# pro-micro-ora.net
KiCad netlist of a schematic drawn in EAGLE
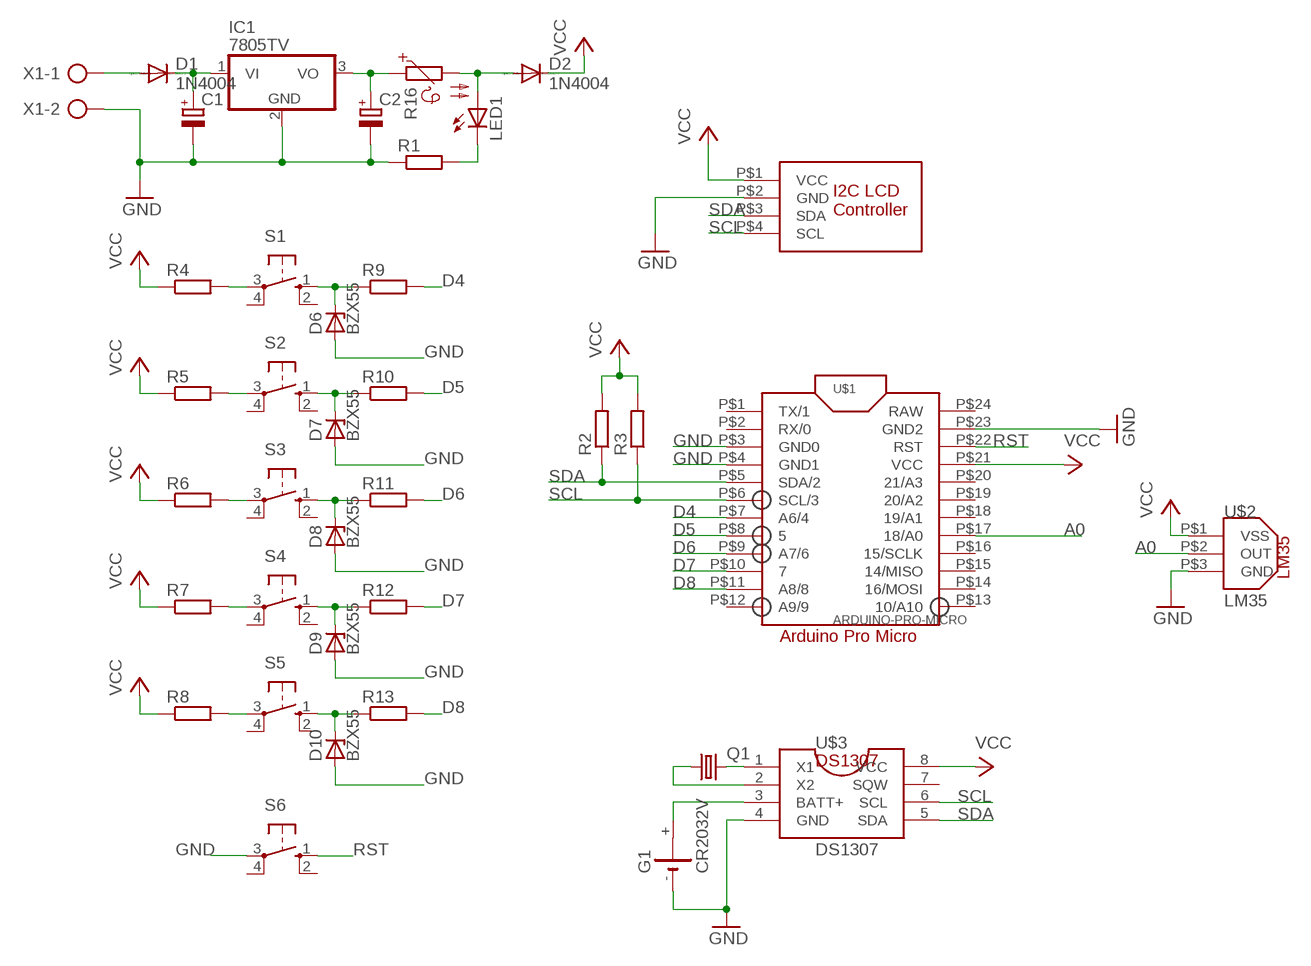
[diagram p0: schematic, sheet 1]

(export (version "E")
  (design (tool "Eeschema 10.0.6"))
  (components
    (comp (ref "C1")
      (value "CPOL-EUE2.5-5")
      (footprint "eagle-import:E2,5-5")
      (libsource (lib "eagle-import") (part "CPOL-EUE2.5-5"))
    )
    (comp (ref "C2")
      (value "CPOL-EUE2.5-5")
      (footprint "eagle-import:E2,5-5")
      (libsource (lib "eagle-import") (part "CPOL-EUE2.5-5"))
    )
    (comp (ref "D1")
      (value "1N4004")
      (footprint "eagle-import:DO41-10")
      (libsource (lib "eagle-import") (part "1N4004"))
    )
    (comp (ref "D2")
      (value "1N4004")
      (footprint "eagle-import:DO41-10")
      (libsource (lib "eagle-import") (part "1N4004"))
    )
    (comp (ref "D6")
      (value "BZX55")
      (footprint "eagle-import:DO35Z10")
      (libsource (lib "eagle-import") (part "BZX55"))
    )
    (comp (ref "D7")
      (value "BZX55")
      (footprint "eagle-import:DO35Z10")
      (libsource (lib "eagle-import") (part "BZX55"))
    )
    (comp (ref "D8")
      (value "BZX55")
      (footprint "eagle-import:DO35Z10")
      (libsource (lib "eagle-import") (part "BZX55"))
    )
    (comp (ref "D9")
      (value "BZX55")
      (footprint "eagle-import:DO35Z10")
      (libsource (lib "eagle-import") (part "BZX55"))
    )
    (comp (ref "D10")
      (value "BZX55")
      (footprint "eagle-import:DO35Z10")
      (libsource (lib "eagle-import") (part "BZX55"))
    )
    (comp (ref "G1")
      (value "CR2032V")
      (footprint "eagle-import:CR2032V")
      (libsource (lib "eagle-import") (part "CR2032V"))
    )
    (comp (ref "IC1")
      (value "7805TV")
      (footprint "eagle-import:TO220V")
      (libsource (lib "eagle-import") (part "78TV05"))
    )
    (comp (ref "LED1")
      (value "LED5MM")
      (footprint "eagle-import:LED5MM")
      (libsource (lib "eagle-import") (part "LED5MM"))
    )
    (comp (ref "Q1")
      (value "CRYSTALTC26H")
      (footprint "eagle-import:TC26H")
      (libsource (lib "eagle-import") (part "CRYSTALTC26H"))
    )
    (comp (ref "R1")
      (value "R-EU_0204/7")
      (footprint "eagle-import:0204_7")
      (libsource (lib "eagle-import") (part "R-EU_0204/7"))
    )
    (comp (ref "R2")
      (value "R-EU_0204/7")
      (footprint "eagle-import:0204_7")
      (libsource (lib "eagle-import") (part "R-EU_0204/7"))
    )
    (comp (ref "R3")
      (value "R-EU_0204/7")
      (footprint "eagle-import:0204_7")
      (libsource (lib "eagle-import") (part "R-EU_0204/7"))
    )
    (comp (ref "R4")
      (value "R-EU_0204/7")
      (footprint "eagle-import:0204_7")
      (libsource (lib "eagle-import") (part "R-EU_0204/7"))
    )
    (comp (ref "R5")
      (value "R-EU_0204/7")
      (footprint "eagle-import:0204_7")
      (libsource (lib "eagle-import") (part "R-EU_0204/7"))
    )
    (comp (ref "R6")
      (value "R-EU_0204/7")
      (footprint "eagle-import:0204_7")
      (libsource (lib "eagle-import") (part "R-EU_0204/7"))
    )
    (comp (ref "R7")
      (value "R-EU_0204/7")
      (footprint "eagle-import:0204_7")
      (libsource (lib "eagle-import") (part "R-EU_0204/7"))
    )
    (comp (ref "R8")
      (value "R-EU_0204/7")
      (footprint "eagle-import:0204_7")
      (libsource (lib "eagle-import") (part "R-EU_0204/7"))
    )
    (comp (ref "R9")
      (value "R-EU_0204/7")
      (footprint "eagle-import:0204_7")
      (libsource (lib "eagle-import") (part "R-EU_0204/7"))
    )
    (comp (ref "R10")
      (value "R-EU_0204/7")
      (footprint "eagle-import:0204_7")
      (libsource (lib "eagle-import") (part "R-EU_0204/7"))
    )
    (comp (ref "R11")
      (value "R-EU_0204/7")
      (footprint "eagle-import:0204_7")
      (libsource (lib "eagle-import") (part "R-EU_0204/7"))
    )
    (comp (ref "R12")
      (value "R-EU_0204/7")
      (footprint "eagle-import:0204_7")
      (libsource (lib "eagle-import") (part "R-EU_0204/7"))
    )
    (comp (ref "R13")
      (value "R-EU_0204/7")
      (footprint "eagle-import:0204_7")
      (libsource (lib "eagle-import") (part "R-EU_0204/7"))
    )
    (comp (ref "R16")
      (value "PTC660")
      (footprint "eagle-import:P660")
      (libsource (lib "eagle-import") (part "PTC660"))
    )
    (comp (ref "S1")
      (value "10-XX")
      (footprint "eagle-import:B3F-10XX")
      (fields (field (name "MPN") "B3F-1000"))
      (libsource (lib "eagle-import") (part "10-XX"))
    )
    (comp (ref "S2")
      (value "10-XX")
      (footprint "eagle-import:B3F-10XX")
      (fields (field (name "MPN") "B3F-1000"))
      (libsource (lib "eagle-import") (part "10-XX"))
    )
    (comp (ref "S3")
      (value "10-XX")
      (footprint "eagle-import:B3F-10XX")
      (fields (field (name "MPN") "B3F-1000"))
      (libsource (lib "eagle-import") (part "10-XX"))
    )
    (comp (ref "S4")
      (value "10-XX")
      (footprint "eagle-import:B3F-10XX")
      (fields (field (name "MPN") "B3F-1000"))
      (libsource (lib "eagle-import") (part "10-XX"))
    )
    (comp (ref "S5")
      (value "10-XX")
      (footprint "eagle-import:B3F-10XX")
      (fields (field (name "MPN") "B3F-1000"))
      (libsource (lib "eagle-import") (part "10-XX"))
    )
    (comp (ref "S6")
      (value "10-XX")
      (footprint "eagle-import:B3F-10XX")
      (fields (field (name "MPN") "B3F-1000"))
      (libsource (lib "eagle-import") (part "10-XX"))
    )
    (comp (ref "U$1")
      (value "ARDUINO-PRO-MICRO")
      (footprint "eagle-import:ARDUINO-PRO-MICRO")
      (libsource (lib "eagle-import") (part "ARDUINO-PRO-MICRO"))
    )
    (comp (ref "U$2")
      (value "LM35")
      (footprint "eagle-import:LM35")
      (libsource (lib "eagle-import") (part "LM35"))
    )
    (comp (ref "U$3")
      (value "DS1307")
      (footprint "eagle-import:DS1307")
      (libsource (lib "eagle-import") (part "DS1307"))
    )
    (comp (ref "U$4")
      (value "I2C_LCD")
      (footprint "eagle-import:I2C_LCD")
      (libsource (lib "eagle-import") (part "I2C_LCD"))
    )
    (comp (ref "X1")
      (value "AK500/2")
      (footprint "eagle-import:AK500_2")
      (libsource (lib "eagle-import") (part "AK500/2"))
    )
  )
  (nets
    (net (code "1") (name "/A0") (class "Default")
      (node (ref "U$1") (pin "P$17") (pinfunction "18/A0_P$17") (pintype "bidirectional"))
      (node (ref "U$2") (pin "P$2") (pinfunction "OUT_P$2") (pintype "output"))
    )
    (net (code "2") (name "/D4") (class "Default")
      (node (ref "R9") (pin "2") (pinfunction "2_2") (pintype "passive"))
      (node (ref "U$1") (pin "P$7") (pinfunction "A6/4_P$7") (pintype "bidirectional"))
    )
    (net (code "3") (name "/D5") (class "Default")
      (node (ref "R10") (pin "2") (pinfunction "2_2") (pintype "passive"))
      (node (ref "U$1") (pin "P$8") (pinfunction "5_P$8") (pintype "bidirectional"))
    )
    (net (code "4") (name "/D6") (class "Default")
      (node (ref "R11") (pin "2") (pinfunction "2_2") (pintype "passive"))
      (node (ref "U$1") (pin "P$9") (pinfunction "A7/6_P$9") (pintype "bidirectional"))
    )
    (net (code "5") (name "/D7") (class "Default")
      (node (ref "R12") (pin "2") (pinfunction "2_2") (pintype "passive"))
      (node (ref "U$1") (pin "P$10") (pinfunction "7_P$10") (pintype "bidirectional"))
    )
    (net (code "6") (name "/D8") (class "Default")
      (node (ref "R13") (pin "2") (pinfunction "2_2") (pintype "passive"))
      (node (ref "U$1") (pin "P$11") (pinfunction "A8/8_P$11") (pintype "bidirectional"))
    )
    (net (code "7") (name "/RAW") (class "Default")
      (node (ref "U$1") (pin "P$24") (pinfunction "RAW_P$24") (pintype "power_in"))
    )
    (net (code "8") (name "/RST") (class "Default")
      (node (ref "S6") (pin "1") (pinfunction "S_1") (pintype "passive"))
      (node (ref "U$1") (pin "P$22") (pinfunction "RST_P$22") (pintype "bidirectional"))
    )
    (net (code "9") (name "/SCL") (class "Default")
      (node (ref "R3") (pin "1") (pinfunction "1_1") (pintype "passive"))
      (node (ref "U$1") (pin "P$6") (pinfunction "SCL/3_P$6") (pintype "bidirectional"))
      (node (ref "U$3") (pin "6") (pinfunction "SCL_6") (pintype "bidirectional"))
      (node (ref "U$4") (pin "P$4") (pinfunction "SCL_P$4") (pintype "bidirectional"))
    )
    (net (code "10") (name "/SDA") (class "Default")
      (node (ref "R2") (pin "1") (pinfunction "1_1") (pintype "passive"))
      (node (ref "U$1") (pin "P$5") (pinfunction "SDA/2_P$5") (pintype "bidirectional"))
      (node (ref "U$3") (pin "5") (pinfunction "SDA_5") (pintype "bidirectional"))
      (node (ref "U$4") (pin "P$3") (pinfunction "SDA_P$3") (pintype "bidirectional"))
    )
    (net (code "11") (name "GND") (class "Default")
      (node (ref "C1") (pin "-") (pinfunction "-_-") (pintype "passive"))
      (node (ref "C2") (pin "-") (pinfunction "-_-") (pintype "passive"))
      (node (ref "D10") (pin "A") (pinfunction "A_A") (pintype "passive"))
      (node (ref "D6") (pin "A") (pinfunction "A_A") (pintype "passive"))
      (node (ref "D7") (pin "A") (pinfunction "A_A") (pintype "passive"))
      (node (ref "D8") (pin "A") (pinfunction "A_A") (pintype "passive"))
      (node (ref "D9") (pin "A") (pinfunction "A_A") (pintype "passive"))
      (node (ref "G1") (pin "-") (pinfunction "-_-") (pintype "passive"))
      (node (ref "IC1") (pin "2") (pinfunction "GND_2") (pintype "passive"))
      (node (ref "R1") (pin "1") (pinfunction "1_1") (pintype "passive"))
      (node (ref "S6") (pin "3") (pinfunction "P_3") (pintype "passive"))
      (node (ref "U$1") (pin "P$23") (pinfunction "GND2_P$23") (pintype "power_in"))
      (node (ref "U$1") (pin "P$3") (pinfunction "GND0_P$3") (pintype "power_in"))
      (node (ref "U$1") (pin "P$4") (pinfunction "GND1_P$4") (pintype "power_in"))
      (node (ref "U$2") (pin "P$3") (pinfunction "GND_P$3") (pintype "power_in"))
      (node (ref "U$3") (pin "4") (pinfunction "GND_4") (pintype "bidirectional"))
      (node (ref "U$4") (pin "P$2") (pinfunction "GND_P$2") (pintype "bidirectional"))
      (node (ref "X1") (pin "2") (pinfunction "KL_2") (pintype "passive"))
    )
    (net (code "12") (name "Net-(D2-PadA)") (class "Default")
      (node (ref "D2") (pin "A") (pinfunction "A_A") (pintype "passive"))
      (node (ref "LED1") (pin "A") (pinfunction "A_A") (pintype "passive"))
      (node (ref "R16") (pin "2") (pinfunction "2_2") (pintype "passive"))
    )
    (net (code "13") (name "Net-(IC1-VI)") (class "Default")
      (node (ref "C1") (pin "+") (pinfunction "+_+") (pintype "passive"))
      (node (ref "D1") (pin "C") (pinfunction "C_C") (pintype "passive"))
      (node (ref "IC1") (pin "1") (pinfunction "VI_1") (pintype "input"))
    )
    (net (code "14") (name "Net-(IC1-VO)") (class "Default")
      (node (ref "C2") (pin "+") (pinfunction "+_+") (pintype "passive"))
      (node (ref "IC1") (pin "3") (pinfunction "VO_3") (pintype "passive"))
      (node (ref "R16") (pin "1") (pinfunction "1_1") (pintype "passive"))
    )
    (net (code "15") (name "Net-(LED1-C)") (class "Default")
      (node (ref "LED1") (pin "K") (pinfunction "C_K") (pintype "passive"))
      (node (ref "R1") (pin "2") (pinfunction "2_2") (pintype "passive"))
    )
    (net (code "16") (name "Net-(S1-P)") (class "Default")
      (node (ref "R4") (pin "2") (pinfunction "2_2") (pintype "passive"))
      (node (ref "S1") (pin "3") (pinfunction "P_3") (pintype "passive"))
    )
    (net (code "17") (name "Net-(S1-S)") (class "Default")
      (node (ref "D6") (pin "C") (pinfunction "C_C") (pintype "passive"))
      (node (ref "R9") (pin "1") (pinfunction "1_1") (pintype "passive"))
      (node (ref "S1") (pin "1") (pinfunction "S_1") (pintype "passive"))
    )
    (net (code "18") (name "Net-(S2-P)") (class "Default")
      (node (ref "R5") (pin "2") (pinfunction "2_2") (pintype "passive"))
      (node (ref "S2") (pin "3") (pinfunction "P_3") (pintype "passive"))
    )
    (net (code "19") (name "Net-(S2-S)") (class "Default")
      (node (ref "D7") (pin "C") (pinfunction "C_C") (pintype "passive"))
      (node (ref "R10") (pin "1") (pinfunction "1_1") (pintype "passive"))
      (node (ref "S2") (pin "1") (pinfunction "S_1") (pintype "passive"))
    )
    (net (code "20") (name "Net-(S3-P)") (class "Default")
      (node (ref "R6") (pin "2") (pinfunction "2_2") (pintype "passive"))
      (node (ref "S3") (pin "3") (pinfunction "P_3") (pintype "passive"))
    )
    (net (code "21") (name "Net-(S3-S)") (class "Default")
      (node (ref "D8") (pin "C") (pinfunction "C_C") (pintype "passive"))
      (node (ref "R11") (pin "1") (pinfunction "1_1") (pintype "passive"))
      (node (ref "S3") (pin "1") (pinfunction "S_1") (pintype "passive"))
    )
    (net (code "22") (name "Net-(S4-P)") (class "Default")
      (node (ref "R7") (pin "2") (pinfunction "2_2") (pintype "passive"))
      (node (ref "S4") (pin "3") (pinfunction "P_3") (pintype "passive"))
    )
    (net (code "23") (name "Net-(S4-S)") (class "Default")
      (node (ref "D9") (pin "C") (pinfunction "C_C") (pintype "passive"))
      (node (ref "R12") (pin "1") (pinfunction "1_1") (pintype "passive"))
      (node (ref "S4") (pin "1") (pinfunction "S_1") (pintype "passive"))
    )
    (net (code "24") (name "Net-(S5-P)") (class "Default")
      (node (ref "R8") (pin "2") (pinfunction "2_2") (pintype "passive"))
      (node (ref "S5") (pin "3") (pinfunction "P_3") (pintype "passive"))
    )
    (net (code "25") (name "Net-(S5-S)") (class "Default")
      (node (ref "D10") (pin "C") (pinfunction "C_C") (pintype "passive"))
      (node (ref "R13") (pin "1") (pinfunction "1_1") (pintype "passive"))
      (node (ref "S5") (pin "1") (pinfunction "S_1") (pintype "passive"))
    )
    (net (code "26") (name "Net-(U$3-BATT+)") (class "Default")
      (node (ref "G1") (pin "+") (pinfunction "+_+") (pintype "passive"))
      (node (ref "U$3") (pin "3") (pinfunction "BATT+_3") (pintype "bidirectional"))
    )
    (net (code "27") (name "Net-(U$3-X1)") (class "Default")
      (node (ref "Q1") (pin "2") (pinfunction "2_2") (pintype "passive"))
      (node (ref "U$3") (pin "1") (pinfunction "X1_1") (pintype "bidirectional"))
    )
    (net (code "28") (name "Net-(U$3-X2)") (class "Default")
      (node (ref "Q1") (pin "1") (pinfunction "1_1") (pintype "passive"))
      (node (ref "U$3") (pin "2") (pinfunction "X2_2") (pintype "bidirectional"))
    )
    (net (code "29") (name "Net-(X1A-KL)") (class "Default")
      (node (ref "D1") (pin "A") (pinfunction "A_A") (pintype "passive"))
      (node (ref "X1") (pin "1") (pinfunction "KL_1") (pintype "passive"))
    )
    (net (code "30") (name "VCC") (class "Default")
      (node (ref "D2") (pin "C") (pinfunction "C_C") (pintype "passive"))
      (node (ref "R2") (pin "2") (pinfunction "2_2") (pintype "passive"))
      (node (ref "R3") (pin "2") (pinfunction "2_2") (pintype "passive"))
      (node (ref "R4") (pin "1") (pinfunction "1_1") (pintype "passive"))
      (node (ref "R5") (pin "1") (pinfunction "1_1") (pintype "passive"))
      (node (ref "R6") (pin "1") (pinfunction "1_1") (pintype "passive"))
      (node (ref "R7") (pin "1") (pinfunction "1_1") (pintype "passive"))
      (node (ref "R8") (pin "1") (pinfunction "1_1") (pintype "passive"))
      (node (ref "U$1") (pin "P$21") (pinfunction "VCC_P$21") (pintype "power_in"))
      (node (ref "U$2") (pin "P$1") (pinfunction "VSS_P$1") (pintype "power_in"))
      (node (ref "U$3") (pin "8") (pinfunction "VCC_8") (pintype "bidirectional"))
      (node (ref "U$4") (pin "P$1") (pinfunction "VCC_P$1") (pintype "bidirectional"))
    )
    (net (code "31") (name "unconnected-(G1-+-Pad+@1)") (class "Default")
      (node (ref "G1") (pin "+@1") (pinfunction "+_+@1") (pintype "passive"))
    )
    (net (code "32") (name "unconnected-(S1-P1-Pad4)") (class "Default")
      (node (ref "S1") (pin "4") (pinfunction "P1_4") (pintype "passive"))
    )
    (net (code "33") (name "unconnected-(S1-S1-Pad2)") (class "Default")
      (node (ref "S1") (pin "2") (pinfunction "S1_2") (pintype "passive"))
    )
    (net (code "34") (name "unconnected-(S2-P1-Pad4)") (class "Default")
      (node (ref "S2") (pin "4") (pinfunction "P1_4") (pintype "passive"))
    )
    (net (code "35") (name "unconnected-(S2-S1-Pad2)") (class "Default")
      (node (ref "S2") (pin "2") (pinfunction "S1_2") (pintype "passive"))
    )
    (net (code "36") (name "unconnected-(S3-P1-Pad4)") (class "Default")
      (node (ref "S3") (pin "4") (pinfunction "P1_4") (pintype "passive"))
    )
    (net (code "37") (name "unconnected-(S3-S1-Pad2)") (class "Default")
      (node (ref "S3") (pin "2") (pinfunction "S1_2") (pintype "passive"))
    )
    (net (code "38") (name "unconnected-(S4-P1-Pad4)") (class "Default")
      (node (ref "S4") (pin "4") (pinfunction "P1_4") (pintype "passive"))
    )
    (net (code "39") (name "unconnected-(S4-S1-Pad2)") (class "Default")
      (node (ref "S4") (pin "2") (pinfunction "S1_2") (pintype "passive"))
    )
    (net (code "40") (name "unconnected-(S5-P1-Pad4)") (class "Default")
      (node (ref "S5") (pin "4") (pinfunction "P1_4") (pintype "passive"))
    )
    (net (code "41") (name "unconnected-(S5-S1-Pad2)") (class "Default")
      (node (ref "S5") (pin "2") (pinfunction "S1_2") (pintype "passive"))
    )
    (net (code "42") (name "unconnected-(S6-P1-Pad4)") (class "Default")
      (node (ref "S6") (pin "4") (pinfunction "P1_4") (pintype "passive"))
    )
    (net (code "43") (name "unconnected-(S6-S1-Pad2)") (class "Default")
      (node (ref "S6") (pin "2") (pinfunction "S1_2") (pintype "passive"))
    )
    (net (code "44") (name "unconnected-(U$1-10{slash}A10-PadP$13)") (class "Default")
      (node (ref "U$1") (pin "P$13") (pinfunction "10/A10_P$13") (pintype "bidirectional"))
    )
    (net (code "45") (name "unconnected-(U$1-14{slash}MISO-PadP$15)") (class "Default")
      (node (ref "U$1") (pin "P$15") (pinfunction "14/MISO_P$15") (pintype "bidirectional"))
    )
    (net (code "46") (name "unconnected-(U$1-15{slash}SCLK-PadP$16)") (class "Default")
      (node (ref "U$1") (pin "P$16") (pinfunction "15/SCLK_P$16") (pintype "bidirectional"))
    )
    (net (code "47") (name "unconnected-(U$1-16{slash}MOSI-PadP$14)") (class "Default")
      (node (ref "U$1") (pin "P$14") (pinfunction "16/MOSI_P$14") (pintype "bidirectional"))
    )
    (net (code "48") (name "unconnected-(U$1-19{slash}A1-PadP$18)") (class "Default")
      (node (ref "U$1") (pin "P$18") (pinfunction "19/A1_P$18") (pintype "bidirectional"))
    )
    (net (code "49") (name "unconnected-(U$1-20{slash}A2-PadP$19)") (class "Default")
      (node (ref "U$1") (pin "P$19") (pinfunction "20/A2_P$19") (pintype "bidirectional"))
    )
    (net (code "50") (name "unconnected-(U$1-21{slash}A3-PadP$20)") (class "Default")
      (node (ref "U$1") (pin "P$20") (pinfunction "21/A3_P$20") (pintype "bidirectional"))
    )
    (net (code "51") (name "unconnected-(U$1-A9{slash}9-PadP$12)") (class "Default")
      (node (ref "U$1") (pin "P$12") (pinfunction "A9/9_P$12") (pintype "bidirectional"))
    )
    (net (code "52") (name "unconnected-(U$1-RX{slash}0-PadP$2)") (class "Default")
      (node (ref "U$1") (pin "P$2") (pinfunction "RX/0_P$2") (pintype "bidirectional"))
    )
    (net (code "53") (name "unconnected-(U$1-TX{slash}1-PadP$1)") (class "Default")
      (node (ref "U$1") (pin "P$1") (pinfunction "TX/1_P$1") (pintype "bidirectional"))
    )
    (net (code "54") (name "unconnected-(U$3-SQW-Pad7)") (class "Default")
      (node (ref "U$3") (pin "7") (pinfunction "SQW_7") (pintype "bidirectional"))
    )
  )
)
